# FEU31_Part2.net
KiCad netlist of a schematic drawn in Altium Designer
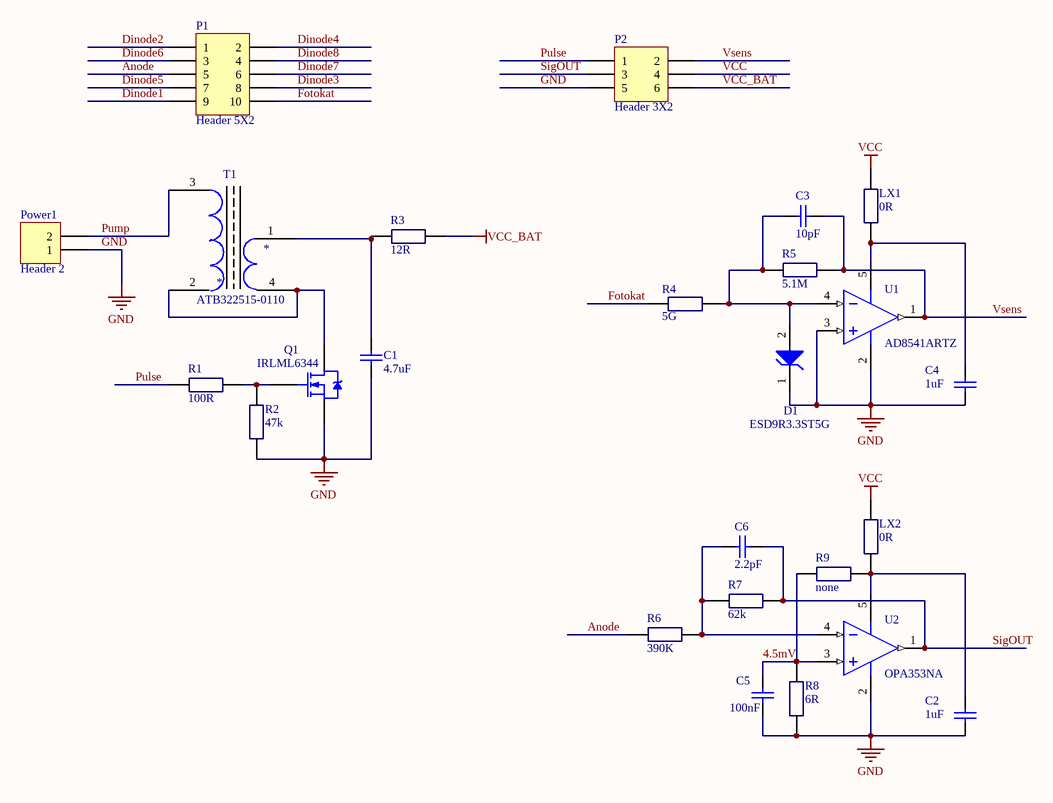
[diagram p0: FEU31_Part2.SchDoc]

(export (version "E")
  (design (tool "Eeschema 10.0.6"))
  (components
    (comp (ref "C1")
      (value "4.7uF")
      (footprint "Miscellaneous Devices:C1206")
      (description "Capacitor (Semiconductor SIM Model)")
      (fields (field (name "PUBLISHER") "Altium Limited"))
      (libsource (lib "Miscellaneous Devices") (part "Cap Semi"))
    )
    (comp (ref "C2")
      (value "1uF")
      (footprint "1608[0603]_CAP")
      (description "Capacitor (Semiconductor SIM Model)")
      (fields (field (name "PUBLISHER") "Altium Limited"))
      (libsource (lib "Miscellaneous Devices") (part "Cap Semi"))
    )
    (comp (ref "C3")
      (value "10pF")
      (footprint "1608[0603]")
      (description "Capacitor (Semiconductor SIM Model)")
      (fields (field (name "PUBLISHER") "Altium Limited"))
      (libsource (lib "Miscellaneous Devices") (part "Cap Semi"))
    )
    (comp (ref "C4")
      (value "1uF")
      (footprint "1608[0603]_CAP")
      (description "Capacitor (Semiconductor SIM Model)")
      (fields (field (name "PUBLISHER") "Altium Limited"))
      (libsource (lib "Miscellaneous Devices") (part "Cap Semi"))
    )
    (comp (ref "C5")
      (value "100nF")
      (footprint "1608[0603]_CAP")
      (description "Capacitor (Semiconductor SIM Model)")
      (fields (field (name "PUBLISHER") "Altium Limited"))
      (libsource (lib "Miscellaneous Devices") (part "Cap Semi"))
    )
    (comp (ref "C6")
      (value "2.2pF")
      (footprint "1608[0603]")
      (description "Capacitor (Semiconductor SIM Model)")
      (fields (field (name "PUBLISHER") "Altium Limited"))
      (libsource (lib "Miscellaneous Devices") (part "Cap Semi"))
    )
    (comp (ref "D1")
      (value "ESD9R3.3ST5G")
      (footprint "ONSC-SOD-923-2-514AB-01_V")
      (fields (field (name "MANUFACTURER") "On Semiconductor"))
      (libsource (lib "ON Semi ESD Protection Diodes & Arrays") (part "ESD9R3.3ST5G"))
    )
    (comp (ref "LX1")
      (value "0R")
      (footprint "1608[0603]")
      (libsource (lib "Микрон-3") (part "Resistor 0805"))
    )
    (comp (ref "LX2")
      (value "0R")
      (footprint "1608[0603]")
      (libsource (lib "Микрон-3") (part "Resistor 0805"))
    )
    (comp (ref "P1")
      (value "Header 5X2")
      (footprint "ФЭУ-31")
      (description "Header, 5-Pin, Dual row")
      (fields (field (name "PUBLISHER") "Altium Limited"))
      (libsource (lib "Miscellaneous Connectors") (part "Header 5X2"))
    )
    (comp (ref "P2")
      (value "Header 3X2")
      (footprint "HDR2X3")
      (description "Header, 3-Pin, Dual row")
      (fields (field (name "PUBLISHER") "Altium Limited"))
      (libsource (lib "Miscellaneous Connectors") (part "Header 3X2"))
    )
    (comp (ref "Power1")
      (value "Header 2")
      (footprint "HDR1X2")
      (description "Header, 2-Pin")
      (fields (field (name "PUBLISHER") "Altium Limited"))
      (libsource (lib "Miscellaneous Connectors") (part "Header 2"))
    )
    (comp (ref "Q1")
      (value "IRLML6344")
      (footprint "SOT-23_N")
      (description "HEXFET Power MOSFET")
      (fields (field (name "PUBLISHER") "Altium Limited"))
      (libsource (lib "IR Discrete MOSFET - Power") (part "IRLML2402"))
    )
    (comp (ref "R1")
      (value "100R")
      (footprint "1608[0603]_RES")
      (libsource (lib "Микрон-3") (part "Resistor 0805"))
    )
    (comp (ref "R2")
      (value "47k")
      (footprint "1608[0603]_RES")
      (libsource (lib "Микрон-3") (part "Resistor 0805"))
    )
    (comp (ref "R3")
      (value "12R")
      (footprint "1608[0603]_RES")
      (libsource (lib "Микрон-3") (part "Resistor 0805"))
    )
    (comp (ref "R4")
      (value "5G")
      (footprint "HVF2512T5007FE")
      (libsource (lib "Микрон-3") (part "Resistor 0805"))
    )
    (comp (ref "R5")
      (value "5.1M")
      (footprint "1608[0603]_RES")
      (libsource (lib "Микрон-3") (part "Resistor 0805"))
    )
    (comp (ref "R6")
      (value "390K")
      (footprint "1608[0603]_RES")
      (libsource (lib "Микрон-3") (part "Resistor 0805"))
    )
    (comp (ref "R7")
      (value "62k")
      (footprint "1608[0603]_RES")
      (libsource (lib "Микрон-3") (part "Resistor 0805"))
    )
    (comp (ref "R8")
      (value "6R")
      (footprint "1608[0603]_RES")
      (libsource (lib "Микрон-3") (part "Resistor 0805"))
    )
    (comp (ref "R9")
      (value "none")
      (footprint "1608[0603]_RES")
      (libsource (lib "Микрон-3") (part "Resistor 0805"))
    )
    (comp (ref "T1")
      (value "ATB322515-0110")
      (footprint "ATB322515-0110")
      (libsource (lib "My SCH library") (part "ATB322515-0110"))
    )
    (comp (ref "U1")
      (value "AD8541ARTZ")
      (footprint "ADI-RJ-5_N")
      (fields
        (field (name "GENERIC PART NUMBER") "AD8541")
        (field (name "MANUFACTURER") "Analog Devices")
        (field (name "PARTNUMBER") "AD8541ARTZ-R2")
      )
      (libsource (lib "Analog Devices Operational Amplifiers") (part "AD8541ARTZ-R2"))
    )
    (comp (ref "U2")
      (value "OPA353NA")
      (footprint "ADI-RJ-5_N")
      (fields
        (field (name "GENERIC PART NUMBER") "AD8541")
        (field (name "MANUFACTURER") "Analog Devices")
        (field (name "PARTNUMBER") "AD8541ARTZ-R2")
      )
      (libsource (lib "Analog Devices Operational Amplifiers") (part "AD8541ARTZ-R2"))
    )
  )
  (nets
    (net (code "1") (name "/4.5mV") (class "Default")
      (node (ref "C5") (pin "1") (pinfunction "1_1") (pintype "passive"))
      (node (ref "R8") (pin "2") (pinfunction "2_2") (pintype "passive"))
      (node (ref "R9") (pin "1") (pinfunction "A_1") (pintype "passive"))
      (node (ref "U2") (pin "3") (pinfunction "+IN_A_3") (pintype "input"))
    )
    (net (code "2") (name "/Anode") (class "Default")
      (node (ref "P1") (pin "5") (pinfunction "5_5") (pintype "passive"))
      (node (ref "R6") (pin "2") (pinfunction "2_2") (pintype "passive"))
    )
    (net (code "3") (name "/Dinode1") (class "Default")
      (node (ref "P1") (pin "9") (pinfunction "9_9") (pintype "passive"))
    )
    (net (code "4") (name "/Dinode2") (class "Default")
      (node (ref "P1") (pin "1") (pinfunction "1_1") (pintype "passive"))
    )
    (net (code "5") (name "/Dinode3") (class "Default")
      (node (ref "P1") (pin "8") (pinfunction "8_8") (pintype "passive"))
    )
    (net (code "6") (name "/Dinode4") (class "Default")
      (node (ref "P1") (pin "2") (pinfunction "2_2") (pintype "passive"))
    )
    (net (code "7") (name "/Dinode5") (class "Default")
      (node (ref "P1") (pin "7") (pinfunction "7_7") (pintype "passive"))
    )
    (net (code "8") (name "/Dinode6") (class "Default")
      (node (ref "P1") (pin "3") (pinfunction "3_3") (pintype "passive"))
    )
    (net (code "9") (name "/Dinode7") (class "Default")
      (node (ref "P1") (pin "6") (pinfunction "6_6") (pintype "passive"))
    )
    (net (code "10") (name "/Dinode8") (class "Default")
      (node (ref "P1") (pin "4") (pinfunction "4_4") (pintype "passive"))
    )
    (net (code "11") (name "/Fotokat") (class "Default")
      (node (ref "P1") (pin "10") (pinfunction "10_10") (pintype "passive"))
      (node (ref "R4") (pin "1") (pinfunction "A_1") (pintype "passive"))
    )
    (net (code "12") (name "/Pulse") (class "Default")
      (node (ref "P2") (pin "1") (pinfunction "1_1") (pintype "passive"))
      (node (ref "R1") (pin "1") (pinfunction "A_1") (pintype "passive"))
    )
    (net (code "13") (name "/Pump") (class "Default")
      (node (ref "Power1") (pin "2") (pinfunction "2_2") (pintype "passive"))
      (node (ref "T1") (pin "3") (pinfunction "3_3") (pintype "passive"))
    )
    (net (code "14") (name "/SigOUT") (class "Default")
      (node (ref "C6") (pin "2") (pinfunction "2_2") (pintype "passive"))
      (node (ref "P2") (pin "3") (pinfunction "3_3") (pintype "passive"))
      (node (ref "R7") (pin "2") (pinfunction "2_2") (pintype "passive"))
      (node (ref "U2") (pin "1") (pinfunction "OUT_A_1") (pintype "output"))
    )
    (net (code "15") (name "/Vsens") (class "Default")
      (node (ref "C3") (pin "2") (pinfunction "2_2") (pintype "passive"))
      (node (ref "P2") (pin "2") (pinfunction "2_2") (pintype "passive"))
      (node (ref "R5") (pin "2") (pinfunction "2_2") (pintype "passive"))
      (node (ref "U1") (pin "1") (pinfunction "OUT_A_1") (pintype "output"))
    )
    (net (code "16") (name "GND") (class "Default")
      (node (ref "C1") (pin "2") (pinfunction "2_2") (pintype "passive"))
      (node (ref "C2") (pin "2") (pinfunction "2_2") (pintype "passive"))
      (node (ref "C4") (pin "2") (pinfunction "2_2") (pintype "passive"))
      (node (ref "C5") (pin "2") (pinfunction "2_2") (pintype "passive"))
      (node (ref "D1") (pin "1") (pinfunction "K_1") (pintype "passive"))
      (node (ref "P2") (pin "5") (pinfunction "5_5") (pintype "passive"))
      (node (ref "Power1") (pin "1") (pinfunction "1_1") (pintype "passive"))
      (node (ref "Q1") (pin "2") (pinfunction "S_2") (pintype "passive"))
      (node (ref "R2") (pin "1") (pinfunction "A_1") (pintype "passive"))
      (node (ref "R8") (pin "1") (pinfunction "A_1") (pintype "passive"))
      (node (ref "U1") (pin "2") (pinfunction "-V_2") (pintype "power_in"))
      (node (ref "U1") (pin "3") (pinfunction "+IN_A_3") (pintype "input"))
      (node (ref "U2") (pin "2") (pinfunction "-V_2") (pintype "power_in"))
    )
    (net (code "17") (name "Net-(D1-A)") (class "Default")
      (node (ref "C3") (pin "1") (pinfunction "1_1") (pintype "passive"))
      (node (ref "D1") (pin "2") (pinfunction "A_2") (pintype "passive"))
      (node (ref "R4") (pin "2") (pinfunction "2_2") (pintype "passive"))
      (node (ref "R5") (pin "1") (pinfunction "A_1") (pintype "passive"))
      (node (ref "U1") (pin "4") (pinfunction "-IN_A_4") (pintype "input"))
    )
    (net (code "18") (name "Net-(Q1-D)") (class "Default")
      (node (ref "Q1") (pin "3") (pinfunction "D_3") (pintype "passive"))
      (node (ref "T1") (pin "2") (pinfunction "2_2") (pintype "passive"))
      (node (ref "T1") (pin "4") (pintype "passive"))
    )
    (net (code "19") (name "Net-(Q1-G)") (class "Default")
      (node (ref "Q1") (pin "1") (pinfunction "G_1") (pintype "passive"))
      (node (ref "R1") (pin "2") (pinfunction "2_2") (pintype "passive"))
      (node (ref "R2") (pin "2") (pinfunction "2_2") (pintype "passive"))
    )
    (net (code "20") (name "Net-(R3-A)") (class "Default")
      (node (ref "C1") (pin "1") (pinfunction "1_1") (pintype "passive"))
      (node (ref "R3") (pin "1") (pinfunction "A_1") (pintype "passive"))
      (node (ref "T1") (pin "1") (pinfunction "1_1") (pintype "passive"))
    )
    (net (code "21") (name "Net-(R6-A)") (class "Default")
      (node (ref "C6") (pin "1") (pinfunction "1_1") (pintype "passive"))
      (node (ref "R6") (pin "1") (pinfunction "A_1") (pintype "passive"))
      (node (ref "R7") (pin "1") (pinfunction "A_1") (pintype "passive"))
      (node (ref "U2") (pin "4") (pinfunction "-IN_A_4") (pintype "input"))
    )
    (net (code "22") (name "Net-(U1-+V)") (class "Default")
      (node (ref "C4") (pin "1") (pinfunction "1_1") (pintype "passive"))
      (node (ref "LX1") (pin "2") (pinfunction "2_2") (pintype "passive"))
      (node (ref "U1") (pin "5") (pinfunction "+V_5") (pintype "power_in"))
    )
    (net (code "23") (name "Net-(U2-+V)") (class "Default")
      (node (ref "C2") (pin "1") (pinfunction "1_1") (pintype "passive"))
      (node (ref "LX2") (pin "2") (pinfunction "2_2") (pintype "passive"))
      (node (ref "R9") (pin "2") (pinfunction "2_2") (pintype "passive"))
      (node (ref "U2") (pin "5") (pinfunction "+V_5") (pintype "power_in"))
    )
    (net (code "24") (name "VCC") (class "Default")
      (node (ref "LX1") (pin "1") (pinfunction "A_1") (pintype "passive"))
      (node (ref "LX2") (pin "1") (pinfunction "A_1") (pintype "passive"))
      (node (ref "P2") (pin "4") (pinfunction "4_4") (pintype "passive"))
    )
    (net (code "25") (name "VCC_BAT") (class "Default")
      (node (ref "P2") (pin "6") (pinfunction "6_6") (pintype "passive"))
      (node (ref "R3") (pin "2") (pinfunction "2_2") (pintype "passive"))
    )
  )
)
